# Lemming2_power_v1_1.net
KiCad netlist of a schematic drawn in EAGLE
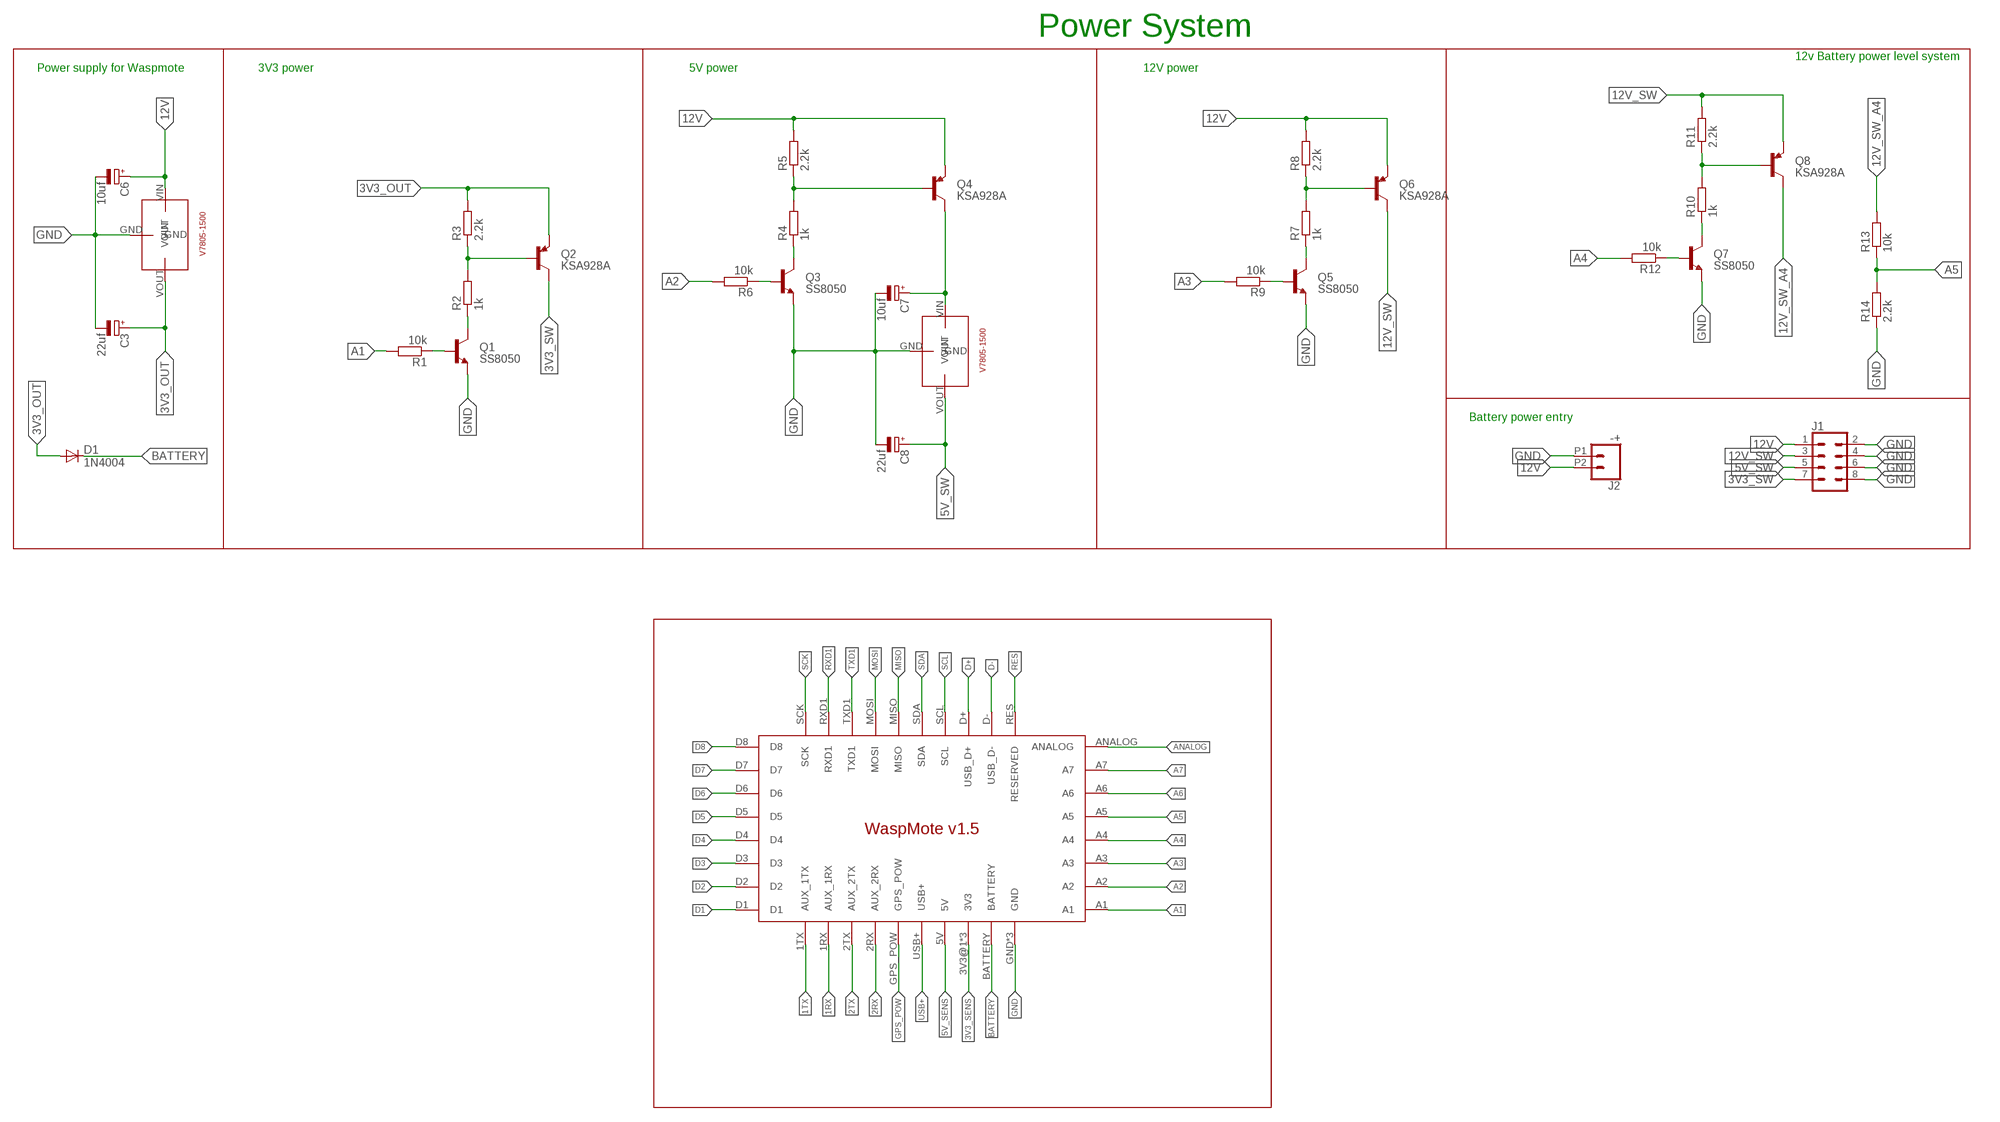
[diagram p0: schematic, sheet 1]

(export (version "E")
  (design (tool "Eeschema 10.0.6"))
  (components
    (comp (ref "C3")
      (value "22uf")
      (footprint "eagle-import:E2,5-5")
      (libsource (lib "eagle-import") (part "CPOL-EUE2.5-5"))
    )
    (comp (ref "C6")
      (value "10uf")
      (footprint "eagle-import:E2,5-5")
      (libsource (lib "eagle-import") (part "CPOL-EUE2.5-5"))
    )
    (comp (ref "C7")
      (value "10uf")
      (footprint "eagle-import:E2,5-5")
      (libsource (lib "eagle-import") (part "CPOL-EUE2.5-5"))
    )
    (comp (ref "C8")
      (value "22uf")
      (footprint "eagle-import:E2,5-5")
      (libsource (lib "eagle-import") (part "CPOL-EUE2.5-5"))
    )
    (comp (ref "D1")
      (value "1N4004")
      (footprint "eagle-import:DO41-10")
      (libsource (lib "eagle-import") (part "1N4004"))
    )
    (comp (ref "J1")
      (value "CONN_04X2")
      (footprint "eagle-import:2X4")
      (libsource (lib "eagle-import") (part "CONN_04X2"))
    )
    (comp (ref "J2")
      (value "-+")
      (footprint "eagle-import:1X02_2.54_SCREWTERM")
      (libsource (lib "eagle-import") (part "CONN_022.54MM_SCREWTERM"))
    )
    (comp (ref "LM7805")
      (value "V7805-1500")
      (footprint "eagle-import:V7805-1500")
      (libsource (lib "eagle-import") (part "V7805-1500"))
    )
    (comp (ref "Q1")
      (value "SS8050")
      (footprint "eagle-import:TO-92-EBC")
      (libsource (lib "eagle-import") (part "SS8050"))
    )
    (comp (ref "Q2")
      (value "KSA928A")
      (footprint "eagle-import:TO-92-ECB")
      (libsource (lib "eagle-import") (part "KSA928A"))
    )
    (comp (ref "Q3")
      (value "SS8050")
      (footprint "eagle-import:TO-92-EBC")
      (libsource (lib "eagle-import") (part "SS8050"))
    )
    (comp (ref "Q4")
      (value "KSA928A")
      (footprint "eagle-import:TO-92-ECB")
      (libsource (lib "eagle-import") (part "KSA928A"))
    )
    (comp (ref "Q5")
      (value "SS8050")
      (footprint "eagle-import:TO-92-EBC")
      (libsource (lib "eagle-import") (part "SS8050"))
    )
    (comp (ref "Q6")
      (value "KSA928A")
      (footprint "eagle-import:TO-92-ECB")
      (libsource (lib "eagle-import") (part "KSA928A"))
    )
    (comp (ref "Q7")
      (value "SS8050")
      (footprint "eagle-import:TO-92-EBC")
      (libsource (lib "eagle-import") (part "SS8050"))
    )
    (comp (ref "Q8")
      (value "KSA928A")
      (footprint "eagle-import:TO-92-ECB")
      (libsource (lib "eagle-import") (part "KSA928A"))
    )
    (comp (ref "R1")
      (value "10k")
      (footprint "eagle-import:RESISTOR_0309_10")
      (libsource (lib "eagle-import") (part "RESISTOR_R-EU_0309/10"))
    )
    (comp (ref "R2")
      (value "1k")
      (footprint "eagle-import:RESISTOR_0309_10")
      (libsource (lib "eagle-import") (part "RESISTOR_R-EU_0309/10"))
    )
    (comp (ref "R3")
      (value "2.2k")
      (footprint "eagle-import:RESISTOR_0309_10")
      (libsource (lib "eagle-import") (part "RESISTOR_R-EU_0309/10"))
    )
    (comp (ref "R4")
      (value "1k")
      (footprint "eagle-import:RESISTOR_0309_10")
      (libsource (lib "eagle-import") (part "RESISTOR_R-EU_0309/10"))
    )
    (comp (ref "R5")
      (value "2.2k")
      (footprint "eagle-import:RESISTOR_0309_10")
      (libsource (lib "eagle-import") (part "RESISTOR_R-EU_0309/10"))
    )
    (comp (ref "R6")
      (value "10k")
      (footprint "eagle-import:RESISTOR_0309_10")
      (libsource (lib "eagle-import") (part "RESISTOR_R-EU_0309/10"))
    )
    (comp (ref "R7")
      (value "1k")
      (footprint "eagle-import:RESISTOR_0309_10")
      (libsource (lib "eagle-import") (part "RESISTOR_R-EU_0309/10"))
    )
    (comp (ref "R8")
      (value "2.2k")
      (footprint "eagle-import:RESISTOR_0309_10")
      (libsource (lib "eagle-import") (part "RESISTOR_R-EU_0309/10"))
    )
    (comp (ref "R9")
      (value "10k")
      (footprint "eagle-import:RESISTOR_0309_10")
      (libsource (lib "eagle-import") (part "RESISTOR_R-EU_0309/10"))
    )
    (comp (ref "R10")
      (value "1k")
      (footprint "eagle-import:RESISTOR_0309_10")
      (libsource (lib "eagle-import") (part "RESISTOR_R-EU_0309/10"))
    )
    (comp (ref "R11")
      (value "2.2k")
      (footprint "eagle-import:RESISTOR_0309_10")
      (libsource (lib "eagle-import") (part "RESISTOR_R-EU_0309/10"))
    )
    (comp (ref "R12")
      (value "10k")
      (footprint "eagle-import:RESISTOR_0309_10")
      (libsource (lib "eagle-import") (part "RESISTOR_R-EU_0309/10"))
    )
    (comp (ref "R13")
      (value "10k")
      (footprint "eagle-import:RESISTOR_0309_10")
      (libsource (lib "eagle-import") (part "RESISTOR_R-EU_0309/10"))
    )
    (comp (ref "R14")
      (value "2.2k")
      (footprint "eagle-import:RESISTOR_0309_10")
      (libsource (lib "eagle-import") (part "RESISTOR_R-EU_0309/10"))
    )
    (comp (ref "U$1")
      (value "WASPMOTE_V1.5")
      (footprint "eagle-import:WASPMOTE_V1.5")
      (libsource (lib "eagle-import") (part "WASPMOTE_V1.5"))
    )
    (comp (ref "U$22")
      (value "V7803-1500")
      (footprint "eagle-import:V7805-1500")
      (libsource (lib "eagle-import") (part "V7805-1500"))
    )
  )
  (nets
    (net (code "1") (name "1RX") (class "Default")
      (node (ref "U$1") (pin "1RX") (pinfunction "AUX_1RX_1RX") (pintype "bidirectional"))
    )
    (net (code "2") (name "1TX") (class "Default")
      (node (ref "U$1") (pin "1TX") (pinfunction "AUX_1TX_1TX") (pintype "bidirectional"))
    )
    (net (code "3") (name "2RX") (class "Default")
      (node (ref "U$1") (pin "2RX") (pinfunction "AUX_2RX_2RX") (pintype "bidirectional"))
    )
    (net (code "4") (name "2TX") (class "Default")
      (node (ref "U$1") (pin "2TX") (pinfunction "AUX_2TX_2TX") (pintype "bidirectional"))
    )
    (net (code "5") (name "3V3_OUT") (class "Default")
      (node (ref "C3") (pin "+") (pinfunction "+_+") (pintype "passive"))
      (node (ref "D1") (pin "A") (pinfunction "A_A") (pintype "passive"))
      (node (ref "Q2") (pin "E") (pinfunction "E_E") (pintype "passive"))
      (node (ref "R3") (pin "2") (pinfunction "2_2") (pintype "passive"))
      (node (ref "U$22") (pin "VOUT") (pinfunction "VOUT_VOUT") (pintype "bidirectional"))
    )
    (net (code "6") (name "3V3_SENS") (class "Default")
      (node (ref "U$1") (pin "3V3@1") (pinfunction "3V3_3V3@1") (pintype "bidirectional"))
      (node (ref "U$1") (pin "3V3@2") (pinfunction "3V3_3V3@2") (pintype "bidirectional"))
      (node (ref "U$1") (pin "3V3@3") (pinfunction "3V3_3V3@3") (pintype "bidirectional"))
    )
    (net (code "7") (name "3V3_SW") (class "Default")
      (node (ref "J1") (pin "7") (pinfunction "7_7") (pintype "passive"))
      (node (ref "Q2") (pin "C") (pinfunction "C_C") (pintype "passive"))
    )
    (net (code "8") (name "5V_SENS") (class "Default")
      (node (ref "U$1") (pin "5V") (pinfunction "5V_5V") (pintype "bidirectional"))
    )
    (net (code "9") (name "5V_SW") (class "Default")
      (node (ref "C8") (pin "+") (pinfunction "+_+") (pintype "passive"))
      (node (ref "J1") (pin "5") (pinfunction "5_5") (pintype "passive"))
      (node (ref "LM7805") (pin "VOUT") (pinfunction "VOUT_VOUT") (pintype "bidirectional"))
    )
    (net (code "10") (name "12V") (class "Default")
      (node (ref "C6") (pin "+") (pinfunction "+_+") (pintype "passive"))
      (node (ref "J1") (pin "1") (pinfunction "1_1") (pintype "passive"))
      (node (ref "J2") (pin "P2") (pinfunction "2_P2") (pintype "passive"))
      (node (ref "Q4") (pin "E") (pinfunction "E_E") (pintype "passive"))
      (node (ref "Q6") (pin "E") (pinfunction "E_E") (pintype "passive"))
      (node (ref "R5") (pin "2") (pinfunction "2_2") (pintype "passive"))
      (node (ref "R8") (pin "2") (pinfunction "2_2") (pintype "passive"))
      (node (ref "U$22") (pin "VIN") (pinfunction "VIN_VIN") (pintype "bidirectional"))
    )
    (net (code "11") (name "12V_SW") (class "Default")
      (node (ref "J1") (pin "3") (pinfunction "3_3") (pintype "passive"))
      (node (ref "Q6") (pin "C") (pinfunction "C_C") (pintype "passive"))
      (node (ref "Q8") (pin "E") (pinfunction "E_E") (pintype "passive"))
      (node (ref "R11") (pin "2") (pinfunction "2_2") (pintype "passive"))
    )
    (net (code "12") (name "12V_SW_A4") (class "Default")
      (node (ref "Q8") (pin "C") (pinfunction "C_C") (pintype "passive"))
      (node (ref "R13") (pin "2") (pinfunction "2_2") (pintype "passive"))
    )
    (net (code "13") (name "A1") (class "Default")
      (node (ref "R1") (pin "2") (pinfunction "2_2") (pintype "passive"))
      (node (ref "U$1") (pin "A1") (pinfunction "A1_A1") (pintype "bidirectional"))
    )
    (net (code "14") (name "A2") (class "Default")
      (node (ref "R6") (pin "2") (pinfunction "2_2") (pintype "passive"))
      (node (ref "U$1") (pin "A2") (pinfunction "A2_A2") (pintype "bidirectional"))
    )
    (net (code "15") (name "A3") (class "Default")
      (node (ref "R9") (pin "2") (pinfunction "2_2") (pintype "passive"))
      (node (ref "U$1") (pin "A3") (pinfunction "A3_A3") (pintype "bidirectional"))
    )
    (net (code "16") (name "A4") (class "Default")
      (node (ref "R12") (pin "2") (pinfunction "2_2") (pintype "passive"))
      (node (ref "U$1") (pin "A4") (pinfunction "A4_A4") (pintype "bidirectional"))
    )
    (net (code "17") (name "A5") (class "Default")
      (node (ref "R13") (pin "1") (pinfunction "1_1") (pintype "passive"))
      (node (ref "R14") (pin "2") (pinfunction "2_2") (pintype "passive"))
      (node (ref "U$1") (pin "A5") (pinfunction "A5_A5") (pintype "bidirectional"))
    )
    (net (code "18") (name "A6") (class "Default")
      (node (ref "U$1") (pin "A6") (pinfunction "A6_A6") (pintype "bidirectional"))
    )
    (net (code "19") (name "A7") (class "Default")
      (node (ref "U$1") (pin "A7") (pinfunction "A7_A7") (pintype "bidirectional"))
    )
    (net (code "20") (name "ANALOG") (class "Default")
      (node (ref "U$1") (pin "ANALOG") (pinfunction "ANALOG_ANALOG") (pintype "bidirectional"))
    )
    (net (code "21") (name "BATTERY") (class "Default")
      (node (ref "D1") (pin "C") (pinfunction "C_C") (pintype "passive"))
      (node (ref "U$1") (pin "BATTERY") (pinfunction "BATTERY_BATTERY") (pintype "bidirectional"))
    )
    (net (code "22") (name "D+") (class "Default")
      (node (ref "U$1") (pin "D+") (pinfunction "USB_D+_D+") (pintype "bidirectional"))
    )
    (net (code "23") (name "D-") (class "Default")
      (node (ref "U$1") (pin "D-") (pinfunction "USB_D-_D-") (pintype "bidirectional"))
    )
    (net (code "24") (name "D1") (class "Default")
      (node (ref "U$1") (pin "D1") (pinfunction "D1_D1") (pintype "bidirectional"))
    )
    (net (code "25") (name "D2") (class "Default")
      (node (ref "U$1") (pin "D2") (pinfunction "D2_D2") (pintype "bidirectional"))
    )
    (net (code "26") (name "D3") (class "Default")
      (node (ref "U$1") (pin "D3") (pinfunction "D3_D3") (pintype "bidirectional"))
    )
    (net (code "27") (name "D4") (class "Default")
      (node (ref "U$1") (pin "D4") (pinfunction "D4_D4") (pintype "bidirectional"))
    )
    (net (code "28") (name "D5") (class "Default")
      (node (ref "U$1") (pin "D5") (pinfunction "D5_D5") (pintype "bidirectional"))
    )
    (net (code "29") (name "D6") (class "Default")
      (node (ref "U$1") (pin "D6") (pinfunction "D6_D6") (pintype "bidirectional"))
    )
    (net (code "30") (name "D7") (class "Default")
      (node (ref "U$1") (pin "D7") (pinfunction "D7_D7") (pintype "bidirectional"))
    )
    (net (code "31") (name "D8") (class "Default")
      (node (ref "U$1") (pin "D8") (pinfunction "D8_D8") (pintype "bidirectional"))
    )
    (net (code "32") (name "GND") (class "Default")
      (node (ref "C3") (pin "-") (pinfunction "-_-") (pintype "passive"))
      (node (ref "C6") (pin "-") (pinfunction "-_-") (pintype "passive"))
      (node (ref "C7") (pin "-") (pinfunction "-_-") (pintype "passive"))
      (node (ref "C8") (pin "-") (pinfunction "-_-") (pintype "passive"))
      (node (ref "J1") (pin "2") (pinfunction "2_2") (pintype "passive"))
      (node (ref "J1") (pin "4") (pinfunction "4_4") (pintype "passive"))
      (node (ref "J1") (pin "6") (pinfunction "6_6") (pintype "passive"))
      (node (ref "J1") (pin "8") (pinfunction "8_8") (pintype "passive"))
      (node (ref "J2") (pin "P1") (pinfunction "1_P1") (pintype "passive"))
      (node (ref "LM7805") (pin "GND") (pinfunction "GND_GND") (pintype "bidirectional"))
      (node (ref "Q1") (pin "E") (pinfunction "E_E") (pintype "passive"))
      (node (ref "Q3") (pin "E") (pinfunction "E_E") (pintype "passive"))
      (node (ref "Q5") (pin "E") (pinfunction "E_E") (pintype "passive"))
      (node (ref "Q7") (pin "E") (pinfunction "E_E") (pintype "passive"))
      (node (ref "R14") (pin "1") (pinfunction "1_1") (pintype "passive"))
      (node (ref "U$1") (pin "GND") (pinfunction "GND_GND") (pintype "bidirectional"))
      (node (ref "U$1") (pin "GND_2") (pinfunction "GND_GND_2") (pintype "bidirectional"))
      (node (ref "U$1") (pin "USB-") (pinfunction "GND_USB-") (pintype "bidirectional"))
      (node (ref "U$22") (pin "GND") (pinfunction "GND_GND") (pintype "bidirectional"))
    )
    (net (code "33") (name "GPS_POW") (class "Default")
      (node (ref "U$1") (pin "GPS_POW") (pinfunction "GPS_POW_GPS_POW") (pintype "bidirectional"))
    )
    (net (code "34") (name "MISO") (class "Default")
      (node (ref "U$1") (pin "MISO") (pinfunction "MISO_MISO") (pintype "bidirectional"))
    )
    (net (code "35") (name "MOSI") (class "Default")
      (node (ref "U$1") (pin "MOSI") (pinfunction "MOSI_MOSI") (pintype "bidirectional"))
    )
    (net (code "36") (name "Net-(C7-Pad+)") (class "Default")
      (node (ref "C7") (pin "+") (pinfunction "+_+") (pintype "passive"))
      (node (ref "LM7805") (pin "VIN") (pinfunction "VIN_VIN") (pintype "bidirectional"))
      (node (ref "Q4") (pin "C") (pinfunction "C_C") (pintype "passive"))
    )
    (net (code "37") (name "Net-(Q1-PadB)") (class "Default")
      (node (ref "Q1") (pin "B") (pinfunction "B_B") (pintype "passive"))
      (node (ref "R1") (pin "1") (pinfunction "1_1") (pintype "passive"))
    )
    (net (code "38") (name "Net-(Q1-PadC)") (class "Default")
      (node (ref "Q1") (pin "C") (pinfunction "C_C") (pintype "passive"))
      (node (ref "R2") (pin "1") (pinfunction "1_1") (pintype "passive"))
    )
    (net (code "39") (name "Net-(Q2-PadB)") (class "Default")
      (node (ref "Q2") (pin "B") (pinfunction "B_B") (pintype "passive"))
      (node (ref "R2") (pin "2") (pinfunction "2_2") (pintype "passive"))
      (node (ref "R3") (pin "1") (pinfunction "1_1") (pintype "passive"))
    )
    (net (code "40") (name "Net-(Q3-PadB)") (class "Default")
      (node (ref "Q3") (pin "B") (pinfunction "B_B") (pintype "passive"))
      (node (ref "R6") (pin "1") (pinfunction "1_1") (pintype "passive"))
    )
    (net (code "41") (name "Net-(Q3-PadC)") (class "Default")
      (node (ref "Q3") (pin "C") (pinfunction "C_C") (pintype "passive"))
      (node (ref "R4") (pin "1") (pinfunction "1_1") (pintype "passive"))
    )
    (net (code "42") (name "Net-(Q4-PadB)") (class "Default")
      (node (ref "Q4") (pin "B") (pinfunction "B_B") (pintype "passive"))
      (node (ref "R4") (pin "2") (pinfunction "2_2") (pintype "passive"))
      (node (ref "R5") (pin "1") (pinfunction "1_1") (pintype "passive"))
    )
    (net (code "43") (name "Net-(Q5-PadB)") (class "Default")
      (node (ref "Q5") (pin "B") (pinfunction "B_B") (pintype "passive"))
      (node (ref "R9") (pin "1") (pinfunction "1_1") (pintype "passive"))
    )
    (net (code "44") (name "Net-(Q5-PadC)") (class "Default")
      (node (ref "Q5") (pin "C") (pinfunction "C_C") (pintype "passive"))
      (node (ref "R7") (pin "1") (pinfunction "1_1") (pintype "passive"))
    )
    (net (code "45") (name "Net-(Q6-PadB)") (class "Default")
      (node (ref "Q6") (pin "B") (pinfunction "B_B") (pintype "passive"))
      (node (ref "R7") (pin "2") (pinfunction "2_2") (pintype "passive"))
      (node (ref "R8") (pin "1") (pinfunction "1_1") (pintype "passive"))
    )
    (net (code "46") (name "Net-(Q7-PadB)") (class "Default")
      (node (ref "Q7") (pin "B") (pinfunction "B_B") (pintype "passive"))
      (node (ref "R12") (pin "1") (pinfunction "1_1") (pintype "passive"))
    )
    (net (code "47") (name "Net-(Q7-PadC)") (class "Default")
      (node (ref "Q7") (pin "C") (pinfunction "C_C") (pintype "passive"))
      (node (ref "R10") (pin "1") (pinfunction "1_1") (pintype "passive"))
    )
    (net (code "48") (name "Net-(Q8-PadB)") (class "Default")
      (node (ref "Q8") (pin "B") (pinfunction "B_B") (pintype "passive"))
      (node (ref "R10") (pin "2") (pinfunction "2_2") (pintype "passive"))
      (node (ref "R11") (pin "1") (pinfunction "1_1") (pintype "passive"))
    )
    (net (code "49") (name "RES") (class "Default")
      (node (ref "U$1") (pin "RES") (pinfunction "RESERVED_RES") (pintype "bidirectional"))
    )
    (net (code "50") (name "RXD1") (class "Default")
      (node (ref "U$1") (pin "RXD1") (pinfunction "RXD1_RXD1") (pintype "bidirectional"))
    )
    (net (code "51") (name "SCK") (class "Default")
      (node (ref "U$1") (pin "SCK") (pinfunction "SCK_SCK") (pintype "bidirectional"))
    )
    (net (code "52") (name "SCL") (class "Default")
      (node (ref "U$1") (pin "SCL") (pinfunction "SCL_SCL") (pintype "bidirectional"))
    )
    (net (code "53") (name "SDA") (class "Default")
      (node (ref "U$1") (pin "SDA") (pinfunction "SDA_SDA") (pintype "bidirectional"))
    )
    (net (code "54") (name "TXD1") (class "Default")
      (node (ref "U$1") (pin "TXD1") (pinfunction "TXD1_TXD1") (pintype "bidirectional"))
    )
    (net (code "55") (name "USB+") (class "Default")
      (node (ref "U$1") (pin "USB+") (pinfunction "USB+_USB+") (pintype "bidirectional"))
    )
  )
)
